# baby_monitor_v2.net
KiCad netlist of a schematic drawn in EAGLE
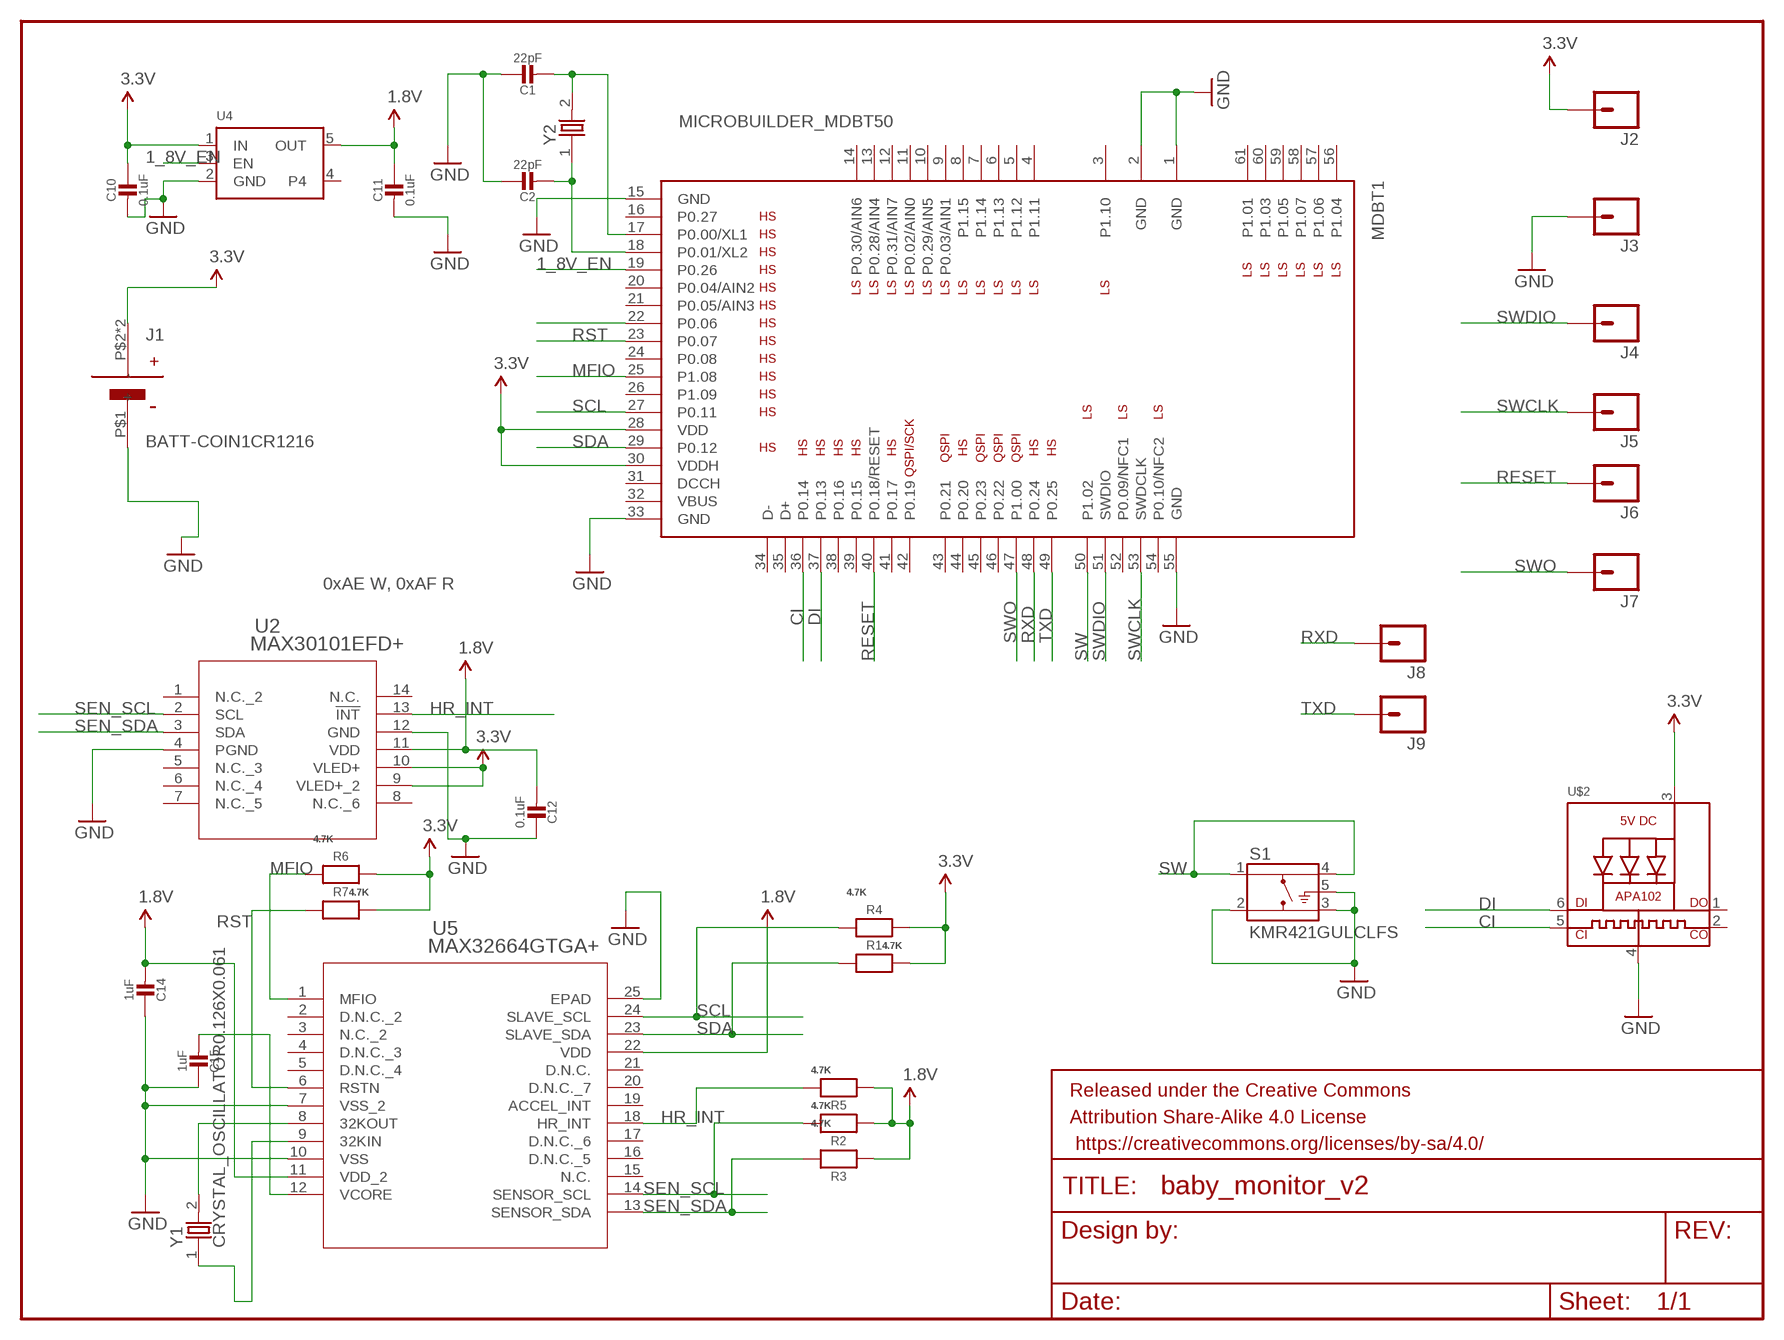
[diagram p0: schematic, sheet 1]

(export (version "E")
  (design (tool "Eeschema 10.0.6"))
  (components
    (comp (ref "C1")
      (value "22pF")
      (footprint "eagle-import:MICROBUILDER__0402MP")
      (libsource (lib "eagle-import") (part "MICROBUILDER_CAP_CERAMIC_0402MP"))
    )
    (comp (ref "C2")
      (value "22pF")
      (footprint "eagle-import:MICROBUILDER__0402MP")
      (libsource (lib "eagle-import") (part "MICROBUILDER_CAP_CERAMIC_0402MP"))
    )
    (comp (ref "C10")
      (value "0.1uF")
      (footprint "eagle-import:MICROBUILDER__0402MP")
      (libsource (lib "eagle-import") (part "MICROBUILDER_CAP_CERAMIC_0402MP"))
    )
    (comp (ref "C11")
      (value "0.1uF")
      (footprint "eagle-import:MICROBUILDER__0402MP")
      (libsource (lib "eagle-import") (part "MICROBUILDER_CAP_CERAMIC_0402MP"))
    )
    (comp (ref "C12")
      (value "0.1uF")
      (footprint "eagle-import:MICROBUILDER__0402MP")
      (libsource (lib "eagle-import") (part "MICROBUILDER_CAP_CERAMIC_0402MP"))
    )
    (comp (ref "C14")
      (value "1uF")
      (footprint "eagle-import:MICROBUILDER__0402MP")
      (libsource (lib "eagle-import") (part "MICROBUILDER_CAP_CERAMIC_0402MP"))
    )
    (comp (ref "C15")
      (value "1uF")
      (footprint "eagle-import:MICROBUILDER__0402MP")
      (libsource (lib "eagle-import") (part "MICROBUILDER_CAP_CERAMIC_0402MP"))
    )
    (comp (ref "FRAME2")
      (value "FRAME-LETTERNO_PACKAGE")
      (footprint "eagle-import:DUMMY")
      (fields (field (name "DESIGNER") "Nobody"))
      (libsource (lib "eagle-import") (part "FRAME-LETTERNO_PACKAGE"))
    )
    (comp (ref "J1")
      (value "BATT-COIN1CR1216")
      (footprint "eagle-import:BC-2017-TR")
      (libsource (lib "eagle-import") (part "BATT-COIN1CR1216"))
    )
    (comp (ref "J2")
      (value "M01TINY")
      (footprint "eagle-import:1X01_TINY")
      (libsource (lib "eagle-import") (part "M01TINY"))
    )
    (comp (ref "J3")
      (value "M01TINY")
      (footprint "eagle-import:1X01_TINY")
      (libsource (lib "eagle-import") (part "M01TINY"))
    )
    (comp (ref "J4")
      (value "M01TINY")
      (footprint "eagle-import:1X01_TINY")
      (libsource (lib "eagle-import") (part "M01TINY"))
    )
    (comp (ref "J5")
      (value "M01TINY")
      (footprint "eagle-import:1X01_TINY")
      (libsource (lib "eagle-import") (part "M01TINY"))
    )
    (comp (ref "J6")
      (value "M01TINY")
      (footprint "eagle-import:1X01_TINY")
      (libsource (lib "eagle-import") (part "M01TINY"))
    )
    (comp (ref "J7")
      (value "M01TINY")
      (footprint "eagle-import:1X01_TINY")
      (libsource (lib "eagle-import") (part "M01TINY"))
    )
    (comp (ref "J8")
      (value "M01TINY_SMD_EXT")
      (footprint "eagle-import:1X01_SMD_TINY_EXT")
      (libsource (lib "eagle-import") (part "M01TINY_SMD_EXT"))
    )
    (comp (ref "J9")
      (value "M01TINY_SMD_EXT")
      (footprint "eagle-import:1X01_SMD_TINY_EXT")
      (libsource (lib "eagle-import") (part "M01TINY_SMD_EXT"))
    )
    (comp (ref "MDBT1")
      (value "MICROBUILDER_MDBT50")
      (footprint "eagle-import:MICROBUILDER_MDBT50")
      (libsource (lib "eagle-import") (part "MICROBUILDER_MDBT50"))
    )
    (comp (ref "R1")
      (value "4.7K")
      (footprint "eagle-import:MICROBUILDER__0402MP")
      (libsource (lib "eagle-import") (part "MICROBUILDER_RESISTOR_0402MP"))
    )
    (comp (ref "R2")
      (value "4.7K")
      (footprint "eagle-import:MICROBUILDER__0402MP")
      (libsource (lib "eagle-import") (part "MICROBUILDER_RESISTOR_0402MP"))
    )
    (comp (ref "R3")
      (value "4.7K")
      (footprint "eagle-import:MICROBUILDER__0402MP")
      (libsource (lib "eagle-import") (part "MICROBUILDER_RESISTOR_0402MP"))
    )
    (comp (ref "R4")
      (value "4.7K")
      (footprint "eagle-import:MICROBUILDER__0402MP")
      (libsource (lib "eagle-import") (part "MICROBUILDER_RESISTOR_0402MP"))
    )
    (comp (ref "R5")
      (value "4.7K")
      (footprint "eagle-import:MICROBUILDER__0402MP")
      (libsource (lib "eagle-import") (part "MICROBUILDER_RESISTOR_0402MP"))
    )
    (comp (ref "R6")
      (value "4.7K")
      (footprint "eagle-import:MICROBUILDER__0402MP")
      (libsource (lib "eagle-import") (part "MICROBUILDER_RESISTOR_0402MP"))
    )
    (comp (ref "R7")
      (value "4.7K")
      (footprint "eagle-import:MICROBUILDER__0402MP")
      (libsource (lib "eagle-import") (part "MICROBUILDER_RESISTOR_0402MP"))
    )
    (comp (ref "S1")
      (value "KMR421GULCLFS")
      (footprint "eagle-import:SW_KMR421GULCLFS")
      (fields (field (name "DIGI-KEY_PART_NUMBER") "CKN12152CT-ND") (field (name "MF") "C&K"))
      (libsource (lib "eagle-import") (part "KMR421GULCLFS"))
    )
    (comp (ref "U$2")
      (value "MICROBUILDER_APA1022020")
      (footprint "eagle-import:MICROBUILDER_APA102_2020")
      (libsource (lib "eagle-import") (part "MICROBUILDER_APA1022020"))
    )
    (comp (ref "U2")
      (value "MAX30101EFD+")
      (footprint "eagle-import:21-0880B_MXM")
      (libsource (lib "eagle-import") (part "MAX30101EFD+"))
    )
    (comp (ref "U4")
      (value "MICROBUILDER_VREG_SOT23-5")
      (footprint "eagle-import:MICROBUILDER_SOT23-5")
      (libsource (lib "eagle-import") (part "MICROBUILDER_VREG_SOT23-5"))
    )
    (comp (ref "U5")
      (value "MAX32664GTGA+")
      (footprint "eagle-import:21-100264_90-100089_MXM")
      (fields (field (name "COPYRIGHT") "Copyright (C) 2018 Accelerated Designs. All rights reserved"))
      (libsource (lib "eagle-import") (part "MAX32664GTGA+"))
    )
    (comp (ref "Y1")
      (value "CRYSTAL_OSCILLATOR0.126X0.061")
      (footprint "eagle-import:QUARTZ")
      (fields (field (name "PARTNO") "SER4072CT-ND "))
      (libsource (lib "eagle-import") (part "CRYSTAL_OSCILLATOR0.126X0.061"))
    )
    (comp (ref "Y2")
      (value "CRYSTAL_OSCILLATOR0.126X0.061")
      (footprint "eagle-import:QUARTZ")
      (fields (field (name "PARTNO") "SER4072CT-ND "))
      (libsource (lib "eagle-import") (part "CRYSTAL_OSCILLATOR0.126X0.061"))
    )
  )
  (nets
    (net (code "1") (name "/1_8V_EN") (class "Default")
      (node (ref "MDBT1") (pin "19") (pinfunction "P0.26_19") (pintype "bidirectional"))
      (node (ref "U4") (pin "3") (pinfunction "EN_3") (pintype "input"))
    )
    (net (code "2") (name "/CI") (class "Default")
      (node (ref "MDBT1") (pin "36") (pinfunction "P0.14_36") (pintype "bidirectional"))
      (node (ref "U$2") (pin "5") (pinfunction "CKI_5") (pintype "input"))
    )
    (net (code "3") (name "/DI") (class "Default")
      (node (ref "MDBT1") (pin "37") (pinfunction "P0.13_37") (pintype "bidirectional"))
      (node (ref "U$2") (pin "6") (pinfunction "DI_6") (pintype "input"))
    )
    (net (code "4") (name "/HR_INT") (class "Default")
      (node (ref "R5") (pin "2") (pinfunction "2_2") (pintype "passive"))
      (node (ref "U2") (pin "13") (pinfunction "~{INT}_13") (pintype "passive"))
      (node (ref "U5") (pin "18") (pinfunction "HR_INT_18") (pintype "input"))
    )
    (net (code "5") (name "/MFIO") (class "Default")
      (node (ref "MDBT1") (pin "25") (pinfunction "P1.08_25") (pintype "bidirectional"))
      (node (ref "R6") (pin "1") (pinfunction "1_1") (pintype "passive"))
      (node (ref "U5") (pin "1") (pinfunction "MFIO_1") (pintype "bidirectional"))
    )
    (net (code "6") (name "/RESET") (class "Default")
      (node (ref "J6") (pin "P$1") (pinfunction "1_P$1") (pintype "passive"))
      (node (ref "MDBT1") (pin "40") (pinfunction "P0.18/RESET_40") (pintype "bidirectional"))
    )
    (net (code "7") (name "/RST") (class "Default")
      (node (ref "MDBT1") (pin "23") (pinfunction "P0.07_23") (pintype "bidirectional"))
      (node (ref "R7") (pin "1") (pinfunction "1_1") (pintype "passive"))
      (node (ref "U5") (pin "6") (pinfunction "RSTN_6") (pintype "input"))
    )
    (net (code "8") (name "/RXD") (class "Default")
      (node (ref "J8") (pin "P$1") (pinfunction "1_P$1") (pintype "passive"))
      (node (ref "MDBT1") (pin "48") (pinfunction "P0.24_48") (pintype "bidirectional"))
    )
    (net (code "9") (name "/SCL") (class "Default")
      (node (ref "MDBT1") (pin "27") (pinfunction "P0.11_27") (pintype "bidirectional"))
      (node (ref "R4") (pin "1") (pinfunction "1_1") (pintype "passive"))
      (node (ref "U5") (pin "24") (pinfunction "SLAVE_SCL_24") (pintype "passive"))
    )
    (net (code "10") (name "/SDA") (class "Default")
      (node (ref "MDBT1") (pin "29") (pinfunction "P0.12_29") (pintype "bidirectional"))
      (node (ref "R1") (pin "1") (pinfunction "1_1") (pintype "passive"))
      (node (ref "U5") (pin "23") (pinfunction "SLAVE_SDA_23") (pintype "passive"))
    )
    (net (code "11") (name "/SEN_SCL") (class "Default")
      (node (ref "R2") (pin "2") (pinfunction "2_2") (pintype "passive"))
      (node (ref "U2") (pin "2") (pinfunction "SCL_2") (pintype "passive"))
      (node (ref "U5") (pin "14") (pinfunction "SENSOR_SCL_14") (pintype "passive"))
    )
    (net (code "12") (name "/SEN_SDA") (class "Default")
      (node (ref "R3") (pin "2") (pinfunction "2_2") (pintype "passive"))
      (node (ref "U2") (pin "3") (pinfunction "SDA_3") (pintype "passive"))
      (node (ref "U5") (pin "13") (pinfunction "SENSOR_SDA_13") (pintype "passive"))
    )
    (net (code "13") (name "/SW") (class "Default")
      (node (ref "MDBT1") (pin "50") (pinfunction "P1.02_50") (pintype "bidirectional"))
      (node (ref "S1") (pin "1") (pinfunction "1_1") (pintype "passive"))
      (node (ref "S1") (pin "4") (pinfunction "4_4") (pintype "passive"))
    )
    (net (code "14") (name "/SWCLK") (class "Default")
      (node (ref "J5") (pin "P$1") (pinfunction "1_P$1") (pintype "passive"))
      (node (ref "MDBT1") (pin "53") (pinfunction "SWDCLK_53") (pintype "bidirectional"))
    )
    (net (code "15") (name "/SWDIO") (class "Default")
      (node (ref "J4") (pin "P$1") (pinfunction "1_P$1") (pintype "passive"))
      (node (ref "MDBT1") (pin "51") (pinfunction "SWDIO_51") (pintype "bidirectional"))
    )
    (net (code "16") (name "/SWO") (class "Default")
      (node (ref "J7") (pin "P$1") (pinfunction "1_P$1") (pintype "passive"))
      (node (ref "MDBT1") (pin "47") (pinfunction "P1.00_47") (pintype "bidirectional"))
    )
    (net (code "17") (name "/TXD") (class "Default")
      (node (ref "J9") (pin "P$1") (pinfunction "1_P$1") (pintype "passive"))
      (node (ref "MDBT1") (pin "49") (pinfunction "P0.25_49") (pintype "bidirectional"))
    )
    (net (code "18") (name "1.8V") (class "Default")
      (node (ref "C11") (pin "1") (pinfunction "1_1") (pintype "passive"))
      (node (ref "C12") (pin "2") (pinfunction "2_2") (pintype "passive"))
      (node (ref "C14") (pin "2") (pinfunction "2_2") (pintype "passive"))
      (node (ref "R2") (pin "1") (pinfunction "1_1") (pintype "passive"))
      (node (ref "R3") (pin "1") (pinfunction "1_1") (pintype "passive"))
      (node (ref "R5") (pin "1") (pinfunction "1_1") (pintype "passive"))
      (node (ref "U2") (pin "11") (pinfunction "VDD_11") (pintype "power_in"))
      (node (ref "U4") (pin "5") (pinfunction "OUT_5") (pintype "power_in"))
      (node (ref "U5") (pin "11") (pinfunction "VDD_2_11") (pintype "power_in"))
      (node (ref "U5") (pin "22") (pinfunction "VDD_22") (pintype "power_in"))
    )
    (net (code "19") (name "3.3V") (class "Default")
      (node (ref "C10") (pin "1") (pinfunction "1_1") (pintype "passive"))
      (node (ref "J1") (pin "P$2") (pinfunction "+_P$2") (pintype "bidirectional"))
      (node (ref "J1") (pin "P$3") (pinfunction "+_P$3") (pintype "bidirectional"))
      (node (ref "J2") (pin "P$1") (pinfunction "1_P$1") (pintype "passive"))
      (node (ref "MDBT1") (pin "28") (pinfunction "VDD_28") (pintype "bidirectional"))
      (node (ref "MDBT1") (pin "30") (pinfunction "VDDH_30") (pintype "bidirectional"))
      (node (ref "R1") (pin "2") (pinfunction "2_2") (pintype "passive"))
      (node (ref "R4") (pin "2") (pinfunction "2_2") (pintype "passive"))
      (node (ref "R6") (pin "2") (pinfunction "2_2") (pintype "passive"))
      (node (ref "R7") (pin "2") (pinfunction "2_2") (pintype "passive"))
      (node (ref "U$2") (pin "3") (pinfunction "VDD_3") (pintype "power_in"))
      (node (ref "U2") (pin "10") (pinfunction "VLED+_10") (pintype "passive"))
      (node (ref "U2") (pin "9") (pinfunction "VLED+_2_9") (pintype "passive"))
      (node (ref "U4") (pin "1") (pinfunction "IN_1") (pintype "power_in"))
    )
    (net (code "20") (name "GND") (class "Default")
      (node (ref "C1") (pin "1") (pinfunction "1_1") (pintype "passive"))
      (node (ref "C10") (pin "2") (pinfunction "2_2") (pintype "passive"))
      (node (ref "C11") (pin "2") (pinfunction "2_2") (pintype "passive"))
      (node (ref "C12") (pin "1") (pinfunction "1_1") (pintype "passive"))
      (node (ref "C14") (pin "1") (pinfunction "1_1") (pintype "passive"))
      (node (ref "C15") (pin "1") (pinfunction "1_1") (pintype "passive"))
      (node (ref "C2") (pin "1") (pinfunction "1_1") (pintype "passive"))
      (node (ref "J1") (pin "P$1") (pinfunction "-_P$1") (pintype "bidirectional"))
      (node (ref "J3") (pin "P$1") (pinfunction "1_P$1") (pintype "passive"))
      (node (ref "MDBT1") (pin "1") (pinfunction "GND_1") (pintype "bidirectional"))
      (node (ref "MDBT1") (pin "15") (pinfunction "GND_15") (pintype "bidirectional"))
      (node (ref "MDBT1") (pin "2") (pinfunction "GND_2") (pintype "bidirectional"))
      (node (ref "MDBT1") (pin "33") (pinfunction "GND_33") (pintype "bidirectional"))
      (node (ref "MDBT1") (pin "55") (pinfunction "GND_55") (pintype "bidirectional"))
      (node (ref "S1") (pin "2") (pinfunction "2_2") (pintype "passive"))
      (node (ref "S1") (pin "3") (pinfunction "3_3") (pintype "passive"))
      (node (ref "S1") (pin "5") (pinfunction "G_5") (pintype "power_in"))
      (node (ref "U$2") (pin "4") (pinfunction "GND_4") (pintype "power_in"))
      (node (ref "U2") (pin "12") (pinfunction "GND_12") (pintype "passive"))
      (node (ref "U2") (pin "4") (pinfunction "PGND_4") (pintype "passive"))
      (node (ref "U4") (pin "2") (pinfunction "GND_2") (pintype "power_in"))
      (node (ref "U5") (pin "10") (pinfunction "VSS_10") (pintype "power_in"))
      (node (ref "U5") (pin "25") (pinfunction "EPAD_25") (pintype "power_in"))
      (node (ref "U5") (pin "7") (pinfunction "VSS_2_7") (pintype "power_in"))
    )
    (net (code "21") (name "Net-(MDBT1-P0.00{slash}XL1)") (class "Default")
      (node (ref "C1") (pin "2") (pinfunction "2_2") (pintype "passive"))
      (node (ref "MDBT1") (pin "17") (pinfunction "P0.00/XL1_17") (pintype "bidirectional"))
      (node (ref "Y2") (pin "2") (pinfunction "2_2") (pintype "passive"))
    )
    (net (code "22") (name "Net-(MDBT1-P0.01{slash}XL2)") (class "Default")
      (node (ref "C2") (pin "2") (pinfunction "2_2") (pintype "passive"))
      (node (ref "MDBT1") (pin "18") (pinfunction "P0.01/XL2_18") (pintype "bidirectional"))
      (node (ref "Y2") (pin "1") (pinfunction "1_1") (pintype "passive"))
    )
    (net (code "23") (name "Net-(U5-32KIN)") (class "Default")
      (node (ref "U5") (pin "9") (pinfunction "32KIN_9") (pintype "input"))
      (node (ref "Y1") (pin "1") (pinfunction "1_1") (pintype "passive"))
    )
    (net (code "24") (name "Net-(U5-32KOUT)") (class "Default")
      (node (ref "U5") (pin "8") (pinfunction "32KOUT_8") (pintype "output"))
      (node (ref "Y1") (pin "2") (pinfunction "2_2") (pintype "passive"))
    )
    (net (code "25") (name "Net-(U5-VCORE)") (class "Default")
      (node (ref "C15") (pin "2") (pinfunction "2_2") (pintype "passive"))
      (node (ref "U5") (pin "12") (pinfunction "VCORE_12") (pintype "power_in"))
    )
    (net (code "26") (name "unconnected-(MDBT1-D+-Pad35)") (class "Default")
      (node (ref "MDBT1") (pin "35") (pinfunction "D+_35") (pintype "bidirectional"))
    )
    (net (code "27") (name "unconnected-(MDBT1-D--Pad34)") (class "Default")
      (node (ref "MDBT1") (pin "34") (pinfunction "D-_34") (pintype "bidirectional"))
    )
    (net (code "28") (name "unconnected-(MDBT1-DCCH-Pad31)") (class "Default")
      (node (ref "MDBT1") (pin "31") (pinfunction "DCCH_31") (pintype "bidirectional"))
    )
    (net (code "29") (name "unconnected-(MDBT1-P0.02{slash}AIN0-Pad11)") (class "Default")
      (node (ref "MDBT1") (pin "11") (pinfunction "P0.02/AIN0_11") (pintype "bidirectional"))
    )
    (net (code "30") (name "unconnected-(MDBT1-P0.03{slash}AIN1-Pad9)") (class "Default")
      (node (ref "MDBT1") (pin "9") (pinfunction "P0.03/AIN1_9") (pintype "bidirectional"))
    )
    (net (code "31") (name "unconnected-(MDBT1-P0.04{slash}AIN2-Pad20)") (class "Default")
      (node (ref "MDBT1") (pin "20") (pinfunction "P0.04/AIN2_20") (pintype "bidirectional"))
    )
    (net (code "32") (name "unconnected-(MDBT1-P0.05{slash}AIN3-Pad21)") (class "Default")
      (node (ref "MDBT1") (pin "21") (pinfunction "P0.05/AIN3_21") (pintype "bidirectional"))
    )
    (net (code "33") (name "unconnected-(MDBT1-P0.06-Pad22)") (class "Default")
      (node (ref "MDBT1") (pin "22") (pinfunction "P0.06_22") (pintype "bidirectional"))
    )
    (net (code "34") (name "unconnected-(MDBT1-P0.08-Pad24)") (class "Default")
      (node (ref "MDBT1") (pin "24") (pinfunction "P0.08_24") (pintype "bidirectional"))
    )
    (net (code "35") (name "unconnected-(MDBT1-P0.09{slash}NFC1-Pad52)") (class "Default")
      (node (ref "MDBT1") (pin "52") (pinfunction "P0.09/NFC1_52") (pintype "bidirectional"))
    )
    (net (code "36") (name "unconnected-(MDBT1-P0.10{slash}NFC2-Pad54)") (class "Default")
      (node (ref "MDBT1") (pin "54") (pinfunction "P0.10/NFC2_54") (pintype "bidirectional"))
    )
    (net (code "37") (name "unconnected-(MDBT1-P0.15-Pad39)") (class "Default")
      (node (ref "MDBT1") (pin "39") (pinfunction "P0.15_39") (pintype "bidirectional"))
    )
    (net (code "38") (name "unconnected-(MDBT1-P0.16-Pad38)") (class "Default")
      (node (ref "MDBT1") (pin "38") (pinfunction "P0.16_38") (pintype "bidirectional"))
    )
    (net (code "39") (name "unconnected-(MDBT1-P0.17-Pad41)") (class "Default")
      (node (ref "MDBT1") (pin "41") (pinfunction "P0.17_41") (pintype "bidirectional"))
    )
    (net (code "40") (name "unconnected-(MDBT1-P0.19-Pad42)") (class "Default")
      (node (ref "MDBT1") (pin "42") (pinfunction "P0.19_42") (pintype "bidirectional"))
    )
    (net (code "41") (name "unconnected-(MDBT1-P0.20-Pad44)") (class "Default")
      (node (ref "MDBT1") (pin "44") (pinfunction "P0.20_44") (pintype "bidirectional"))
    )
    (net (code "42") (name "unconnected-(MDBT1-P0.21-Pad43)") (class "Default")
      (node (ref "MDBT1") (pin "43") (pinfunction "P0.21_43") (pintype "bidirectional"))
    )
    (net (code "43") (name "unconnected-(MDBT1-P0.22-Pad46)") (class "Default")
      (node (ref "MDBT1") (pin "46") (pinfunction "P0.22_46") (pintype "bidirectional"))
    )
    (net (code "44") (name "unconnected-(MDBT1-P0.23-Pad45)") (class "Default")
      (node (ref "MDBT1") (pin "45") (pinfunction "P0.23_45") (pintype "bidirectional"))
    )
    (net (code "45") (name "unconnected-(MDBT1-P0.27-Pad16)") (class "Default")
      (node (ref "MDBT1") (pin "16") (pinfunction "P0.27_16") (pintype "bidirectional"))
    )
    (net (code "46") (name "unconnected-(MDBT1-P0.28{slash}AIN4-Pad13)") (class "Default")
      (node (ref "MDBT1") (pin "13") (pinfunction "P0.28/AIN4_13") (pintype "bidirectional"))
    )
    (net (code "47") (name "unconnected-(MDBT1-P0.29{slash}AIN5-Pad10)") (class "Default")
      (node (ref "MDBT1") (pin "10") (pinfunction "P0.29/AIN5_10") (pintype "bidirectional"))
    )
    (net (code "48") (name "unconnected-(MDBT1-P0.30{slash}AIN6-Pad14)") (class "Default")
      (node (ref "MDBT1") (pin "14") (pinfunction "P0.30/AIN6_14") (pintype "bidirectional"))
    )
    (net (code "49") (name "unconnected-(MDBT1-P0.31{slash}AIN7-Pad12)") (class "Default")
      (node (ref "MDBT1") (pin "12") (pinfunction "P0.31/AIN7_12") (pintype "bidirectional"))
    )
    (net (code "50") (name "unconnected-(MDBT1-P1.01-Pad61)") (class "Default")
      (node (ref "MDBT1") (pin "61") (pinfunction "P1.01_61") (pintype "bidirectional"))
    )
    (net (code "51") (name "unconnected-(MDBT1-P1.03-Pad60)") (class "Default")
      (node (ref "MDBT1") (pin "60") (pinfunction "P1.03_60") (pintype "bidirectional"))
    )
    (net (code "52") (name "unconnected-(MDBT1-P1.04-Pad56)") (class "Default")
      (node (ref "MDBT1") (pin "56") (pinfunction "P1.04_56") (pintype "bidirectional"))
    )
    (net (code "53") (name "unconnected-(MDBT1-P1.05-Pad59)") (class "Default")
      (node (ref "MDBT1") (pin "59") (pinfunction "P1.05_59") (pintype "bidirectional"))
    )
    (net (code "54") (name "unconnected-(MDBT1-P1.06-Pad57)") (class "Default")
      (node (ref "MDBT1") (pin "57") (pinfunction "P1.06_57") (pintype "bidirectional"))
    )
    (net (code "55") (name "unconnected-(MDBT1-P1.07-Pad58)") (class "Default")
      (node (ref "MDBT1") (pin "58") (pinfunction "P1.07_58") (pintype "bidirectional"))
    )
    (net (code "56") (name "unconnected-(MDBT1-P1.09-Pad26)") (class "Default")
      (node (ref "MDBT1") (pin "26") (pinfunction "P1.09_26") (pintype "bidirectional"))
    )
    (net (code "57") (name "unconnected-(MDBT1-P1.10-Pad3)") (class "Default")
      (node (ref "MDBT1") (pin "3") (pinfunction "P1.10_3") (pintype "bidirectional"))
    )
    (net (code "58") (name "unconnected-(MDBT1-P1.11-Pad4)") (class "Default")
      (node (ref "MDBT1") (pin "4") (pinfunction "P1.11_4") (pintype "bidirectional"))
    )
    (net (code "59") (name "unconnected-(MDBT1-P1.12-Pad5)") (class "Default")
      (node (ref "MDBT1") (pin "5") (pinfunction "P1.12_5") (pintype "bidirectional"))
    )
    (net (code "60") (name "unconnected-(MDBT1-P1.13-Pad6)") (class "Default")
      (node (ref "MDBT1") (pin "6") (pinfunction "P1.13_6") (pintype "bidirectional"))
    )
    (net (code "61") (name "unconnected-(MDBT1-P1.14-Pad7)") (class "Default")
      (node (ref "MDBT1") (pin "7") (pinfunction "P1.14_7") (pintype "bidirectional"))
    )
    (net (code "62") (name "unconnected-(MDBT1-P1.15-Pad8)") (class "Default")
      (node (ref "MDBT1") (pin "8") (pinfunction "P1.15_8") (pintype "bidirectional"))
    )
    (net (code "63") (name "unconnected-(MDBT1-VBUS-Pad32)") (class "Default")
      (node (ref "MDBT1") (pin "32") (pinfunction "VBUS_32") (pintype "bidirectional"))
    )
    (net (code "64") (name "unconnected-(U$2-CKO-Pad2)") (class "Default")
      (node (ref "U$2") (pin "2") (pinfunction "CKO_2") (pintype "output"))
    )
    (net (code "65") (name "unconnected-(U$2-DO-Pad1)") (class "Default")
      (node (ref "U$2") (pin "1") (pinfunction "DO_1") (pintype "output"))
    )
    (net (code "66") (name "unconnected-(U2-N.C.-Pad14)") (class "Default")
      (node (ref "U2") (pin "14") (pinfunction "N.C._14") (pintype "no_connect"))
    )
    (net (code "67") (name "unconnected-(U2-N.C._2-Pad1)") (class "Default")
      (node (ref "U2") (pin "1") (pinfunction "N.C._2_1") (pintype "no_connect"))
    )
    (net (code "68") (name "unconnected-(U2-N.C._3-Pad5)") (class "Default")
      (node (ref "U2") (pin "5") (pinfunction "N.C._3_5") (pintype "no_connect"))
    )
    (net (code "69") (name "unconnected-(U2-N.C._4-Pad6)") (class "Default")
      (node (ref "U2") (pin "6") (pinfunction "N.C._4_6") (pintype "no_connect"))
    )
    (net (code "70") (name "unconnected-(U2-N.C._5-Pad7)") (class "Default")
      (node (ref "U2") (pin "7") (pinfunction "N.C._5_7") (pintype "no_connect"))
    )
    (net (code "71") (name "unconnected-(U2-N.C._6-Pad8)") (class "Default")
      (node (ref "U2") (pin "8") (pinfunction "N.C._6_8") (pintype "no_connect"))
    )
    (net (code "72") (name "unconnected-(U4-P4-Pad4)") (class "Default")
      (node (ref "U4") (pin "4") (pinfunction "P4_4") (pintype "bidirectional"))
    )
    (net (code "73") (name "unconnected-(U5-ACCEL_INT-Pad19)") (class "Default")
      (node (ref "U5") (pin "19") (pinfunction "ACCEL_INT_19") (pintype "input"))
    )
    (net (code "74") (name "unconnected-(U5-D.N.C.-Pad21)") (class "Default")
      (node (ref "U5") (pin "21") (pinfunction "D.N.C._21") (pintype "no_connect"))
    )
    (net (code "75") (name "unconnected-(U5-D.N.C._2-Pad2)") (class "Default")
      (node (ref "U5") (pin "2") (pinfunction "D.N.C._2_2") (pintype "no_connect"))
    )
    (net (code "76") (name "unconnected-(U5-D.N.C._3-Pad4)") (class "Default")
      (node (ref "U5") (pin "4") (pinfunction "D.N.C._3_4") (pintype "no_connect"))
    )
    (net (code "77") (name "unconnected-(U5-D.N.C._4-Pad5)") (class "Default")
      (node (ref "U5") (pin "5") (pinfunction "D.N.C._4_5") (pintype "no_connect"))
    )
    (net (code "78") (name "unconnected-(U5-D.N.C._5-Pad16)") (class "Default")
      (node (ref "U5") (pin "16") (pinfunction "D.N.C._5_16") (pintype "no_connect"))
    )
    (net (code "79") (name "unconnected-(U5-D.N.C._6-Pad17)") (class "Default")
      (node (ref "U5") (pin "17") (pinfunction "D.N.C._6_17") (pintype "no_connect"))
    )
    (net (code "80") (name "unconnected-(U5-D.N.C._7-Pad20)") (class "Default")
      (node (ref "U5") (pin "20") (pinfunction "D.N.C._7_20") (pintype "no_connect"))
    )
    (net (code "81") (name "unconnected-(U5-N.C.-Pad15)") (class "Default")
      (node (ref "U5") (pin "15") (pinfunction "N.C._15") (pintype "no_connect"))
    )
    (net (code "82") (name "unconnected-(U5-N.C._2-Pad3)") (class "Default")
      (node (ref "U5") (pin "3") (pinfunction "N.C._2_3") (pintype "no_connect"))
    )
  )
)
